# Sheet1.net
KiCad netlist of a schematic drawn in Altium Designer
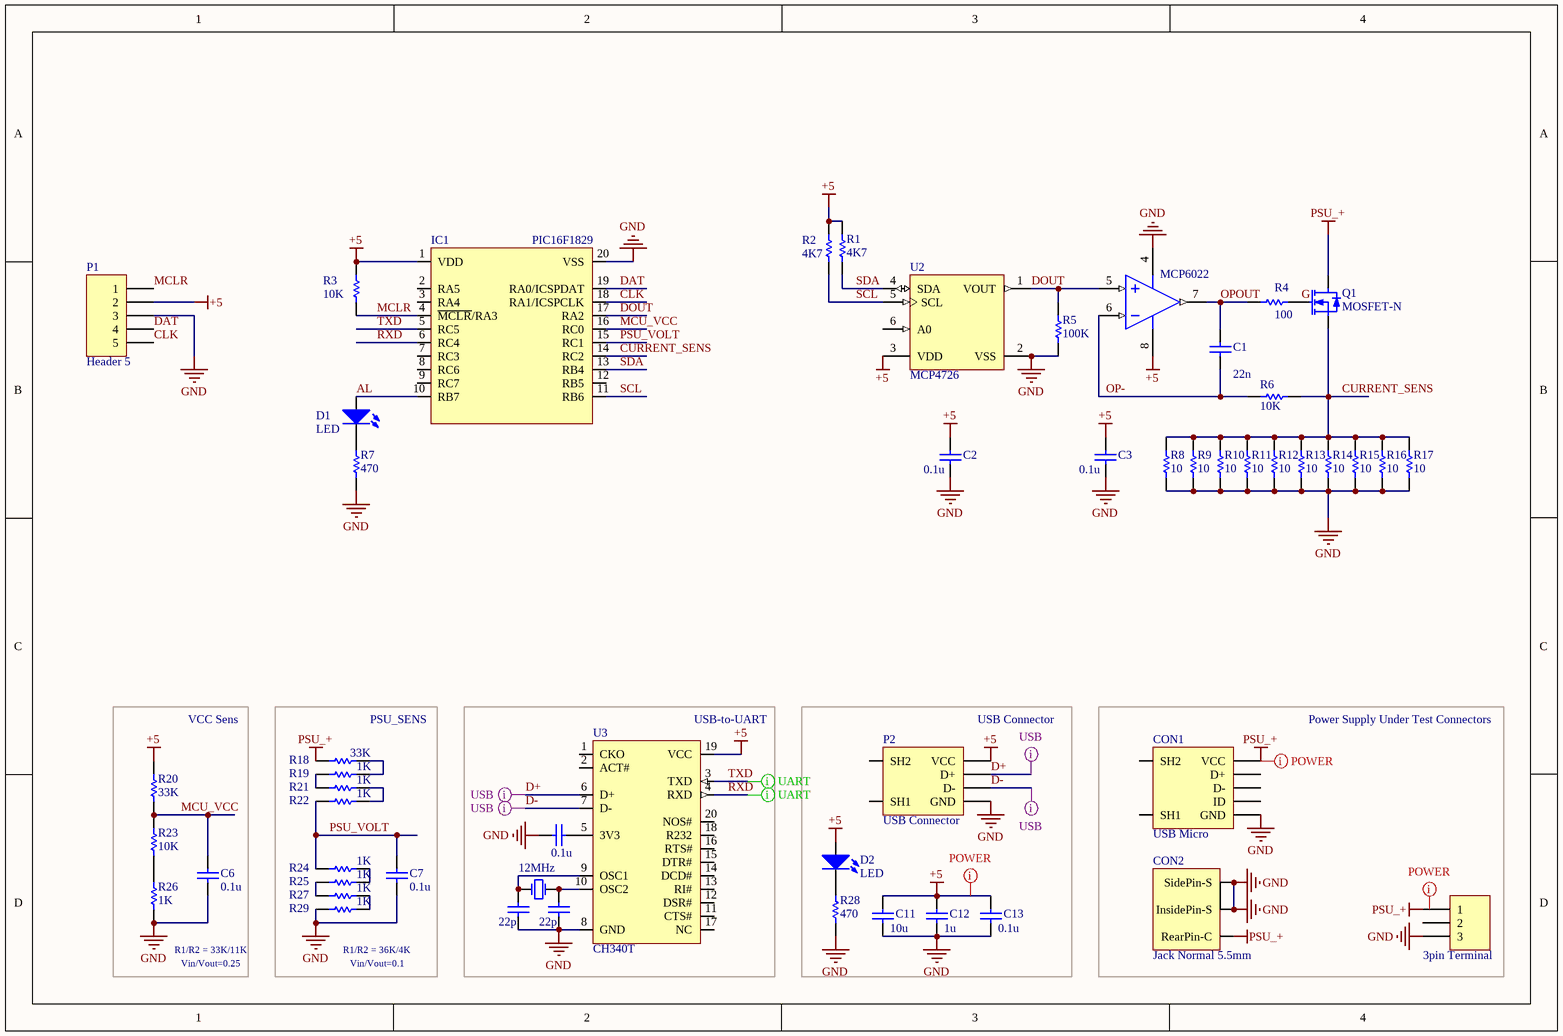
[diagram p0: Sheet1.SchDoc]

(export (version "E")
  (design (tool "Eeschema 10.0.6"))
  (components
    (comp (ref "C1")
      (value "22n")
      (footprint "Moji Footprintovi:0805")
      (description "Capacitor")
      (fields (field (name "Comment") "Cap") (field (name "PUBLISHER") "Altium Limited"))
      (libsource (lib "Moji Schematici") (part "Cap"))
    )
    (comp (ref "C2")
      (value "0.1u")
      (footprint "Moji Footprintovi:0805")
      (description "Capacitor")
      (fields (field (name "Comment") "Cap") (field (name "PUBLISHER") "Altium Limited"))
      (libsource (lib "Moji Schematici") (part "Cap"))
    )
    (comp (ref "C3")
      (value "0.1u")
      (footprint "Moji Footprintovi:0805")
      (description "Capacitor")
      (fields (field (name "Comment") "Cap") (field (name "PUBLISHER") "Altium Limited"))
      (libsource (lib "Moji Schematici") (part "Cap"))
    )
    (comp (ref "C5")
      (value "0.1u")
      (footprint "Moji Footprintovi:0805")
      (description "Capacitor")
      (fields (field (name "Comment") "Cap") (field (name "PUBLISHER") "Altium Limited"))
      (libsource (lib "Moji Schematici") (part "Cap"))
    )
    (comp (ref "C6")
      (value "0.1u")
      (footprint "Moji Footprintovi:0805")
      (description "Capacitor")
      (fields (field (name "Comment") "Cap") (field (name "PUBLISHER") "Altium Limited"))
      (libsource (lib "Moji Schematici") (part "Cap"))
    )
    (comp (ref "C7")
      (value "0.1u")
      (footprint "Moji Footprintovi:0805")
      (description "Capacitor")
      (fields (field (name "Comment") "Cap") (field (name "PUBLISHER") "Altium Limited"))
      (libsource (lib "Moji Schematici") (part "Cap"))
    )
    (comp (ref "C8")
      (value "22p")
      (footprint "Moji Footprintovi:0805")
      (description "Capacitor")
      (fields (field (name "Comment") "Cap") (field (name "PUBLISHER") "Altium Limited"))
      (libsource (lib "Moji Schematici") (part "Cap"))
    )
    (comp (ref "C9")
      (value "22p")
      (footprint "Moji Footprintovi:0805")
      (description "Capacitor")
      (fields (field (name "Comment") "Cap") (field (name "PUBLISHER") "Altium Limited"))
      (libsource (lib "Moji Schematici") (part "Cap"))
    )
    (comp (ref "C11")
      (value "10u")
      (footprint "Moji Footprintovi:0805")
      (description "Capacitor")
      (fields (field (name "Comment") "Cap") (field (name "PUBLISHER") "Altium Limited"))
      (libsource (lib "Moji Schematici") (part "Cap"))
    )
    (comp (ref "C12")
      (value "1u")
      (footprint "Moji Footprintovi:0805")
      (description "Capacitor")
      (fields (field (name "Comment") "Cap") (field (name "PUBLISHER") "Altium Limited"))
      (libsource (lib "Moji Schematici") (part "Cap"))
    )
    (comp (ref "C13")
      (value "0.1u")
      (footprint "Moji Footprintovi:0805")
      (description "Capacitor")
      (fields (field (name "Comment") "Cap") (field (name "PUBLISHER") "Altium Limited"))
      (libsource (lib "Moji Schematici") (part "Cap"))
    )
    (comp (ref "CON1")
      (value "USB Micro")
      (footprint "Moji Footprintovi:USB Micro SMD")
      (description "Header, 4-Pin")
      (fields (field (name "PUBLISHER") "Altium Limited"))
      (libsource (lib "Moji Schematici") (part "USB Micro TH"))
    )
    (comp (ref "CON2")
      (value "Jack Normal 5.5mm")
      (footprint "Jack Normal")
      (description "DC Jack - Center and Side pin Shorted!")
      (libsource (lib "Moji Schematici") (part "Jack Normal 5.5mm"))
    )
    (comp (ref "CON3")
      (value "3pin Terminal")
      (footprint "Terminal 3")
      (description "Header, 3-Pin")
      (fields (field (name "PUBLISHER") "Altium Limited"))
      (libsource (lib "Moji Schematici") (part "Terminal 3"))
    )
    (comp (ref "D1")
      (value "LED")
      (footprint "Moji Footprintovi:LED 5mm [2.54 pin]")
      (description "Typical RED GaAs LED")
      (fields (field (name "PUBLISHER") "Altium Limited"))
      (libsource (lib "Moji Schematici") (part "LED"))
    )
    (comp (ref "D2")
      (value "LED")
      (footprint "Moji Footprintovi:0805 -  LED")
      (description "Typical RED GaAs LED")
      (fields (field (name "PUBLISHER") "Altium Limited"))
      (libsource (lib "Moji Schematici") (part "LED"))
    )
    (comp (ref "IC1")
      (value "PIC16F1829")
      (footprint "Moji Footprintovi:SOP20")
      (libsource (lib "Moji Schematici") (part "PIC16F1829"))
    )
    (comp (ref "P1")
      (value "Header 5")
      (footprint "Moji Footprintovi:Header 5x1")
      (description "Header, 5-Pin")
      (fields (field (name "PUBLISHER") "Altium Limited"))
      (libsource (lib "Moji Schematici") (part "Header 5"))
    )
    (comp (ref "P2")
      (value "USB Connector")
      (footprint "Moji Footprintovi:USB Mini SMD TOP")
      (description "Header, 4-Pin")
      (fields (field (name "PUBLISHER") "Altium Limited"))
      (libsource (lib "Moji Schematici") (part "USB Connector"))
    )
    (comp (ref "Q1")
      (value "MOSFET-N")
      (footprint "Moji Footprintovi:TO-220 w HS2")
      (description "N-Channel MOSFET")
      (fields (field (name "PUBLISHER") "Altium Limited"))
      (libsource (lib "Moji Schematici") (part "MOSFET-N"))
    )
    (comp (ref "R1")
      (value "4K7")
      (footprint "Moji Footprintovi:Axial 0.4")
      (description "Resistor")
      (fields (field (name "Comment") "Res") (field (name "PUBLISHER") "Altium Limited"))
      (libsource (lib "Moji Schematici") (part "Res"))
    )
    (comp (ref "R2")
      (value "4K7")
      (footprint "Moji Footprintovi:Axial 0.4")
      (description "Resistor")
      (fields (field (name "Comment") "Res") (field (name "PUBLISHER") "Altium Limited"))
      (libsource (lib "Moji Schematici") (part "Res"))
    )
    (comp (ref "R3")
      (value "10K")
      (footprint "Moji Footprintovi:0805")
      (description "Resistor")
      (fields (field (name "Comment") "Res") (field (name "PUBLISHER") "Altium Limited"))
      (libsource (lib "Moji Schematici") (part "Res"))
    )
    (comp (ref "R4")
      (value "100")
      (footprint "Moji Footprintovi:0805")
      (description "Resistor")
      (fields (field (name "Comment") "Res") (field (name "PUBLISHER") "Altium Limited"))
      (libsource (lib "Moji Schematici") (part "Res"))
    )
    (comp (ref "R5")
      (value "100K")
      (footprint "Moji Footprintovi:Axial 0.4")
      (description "Resistor")
      (fields (field (name "Comment") "Res") (field (name "PUBLISHER") "Altium Limited"))
      (libsource (lib "Moji Schematici") (part "Res"))
    )
    (comp (ref "R6")
      (value "10K")
      (footprint "Moji Footprintovi:0805")
      (description "Resistor")
      (fields (field (name "Comment") "Res") (field (name "PUBLISHER") "Altium Limited"))
      (libsource (lib "Moji Schematici") (part "Res"))
    )
    (comp (ref "R7")
      (value "470")
      (footprint "Moji Footprintovi:Axial 0.4")
      (description "Resistor")
      (fields (field (name "Comment") "Res") (field (name "PUBLISHER") "Altium Limited"))
      (libsource (lib "Moji Schematici") (part "Res"))
    )
    (comp (ref "R8")
      (value "10")
      (footprint "Moji Footprintovi:Axial 0.4")
      (description "Resistor")
      (fields (field (name "Comment") "Res") (field (name "PUBLISHER") "Altium Limited"))
      (libsource (lib "Moji Schematici") (part "Res"))
    )
    (comp (ref "R9")
      (value "10")
      (footprint "Moji Footprintovi:Axial 0.4")
      (description "Resistor")
      (fields (field (name "Comment") "Res") (field (name "PUBLISHER") "Altium Limited"))
      (libsource (lib "Moji Schematici") (part "Res"))
    )
    (comp (ref "R10")
      (value "10")
      (footprint "Moji Footprintovi:Axial 0.4")
      (description "Resistor")
      (fields (field (name "Comment") "Res") (field (name "PUBLISHER") "Altium Limited"))
      (libsource (lib "Moji Schematici") (part "Res"))
    )
    (comp (ref "R11")
      (value "10")
      (footprint "Moji Footprintovi:Axial 0.4")
      (description "Resistor")
      (fields (field (name "Comment") "Res") (field (name "PUBLISHER") "Altium Limited"))
      (libsource (lib "Moji Schematici") (part "Res"))
    )
    (comp (ref "R12")
      (value "10")
      (footprint "Moji Footprintovi:Axial 0.4")
      (description "Resistor")
      (fields (field (name "Comment") "Res") (field (name "PUBLISHER") "Altium Limited"))
      (libsource (lib "Moji Schematici") (part "Res"))
    )
    (comp (ref "R13")
      (value "10")
      (footprint "Moji Footprintovi:Axial 0.4")
      (description "Resistor")
      (fields (field (name "Comment") "Res") (field (name "PUBLISHER") "Altium Limited"))
      (libsource (lib "Moji Schematici") (part "Res"))
    )
    (comp (ref "R14")
      (value "10")
      (footprint "Moji Footprintovi:Axial 0.4")
      (description "Resistor")
      (fields (field (name "Comment") "Res") (field (name "PUBLISHER") "Altium Limited"))
      (libsource (lib "Moji Schematici") (part "Res"))
    )
    (comp (ref "R15")
      (value "10")
      (footprint "Moji Footprintovi:Axial 0.4")
      (description "Resistor")
      (fields (field (name "Comment") "Res") (field (name "PUBLISHER") "Altium Limited"))
      (libsource (lib "Moji Schematici") (part "Res"))
    )
    (comp (ref "R16")
      (value "10")
      (footprint "Moji Footprintovi:Axial 0.4")
      (description "Resistor")
      (fields (field (name "Comment") "Res") (field (name "PUBLISHER") "Altium Limited"))
      (libsource (lib "Moji Schematici") (part "Res"))
    )
    (comp (ref "R17")
      (value "10")
      (footprint "Moji Footprintovi:Axial 0.4")
      (description "Resistor")
      (fields (field (name "Comment") "Res") (field (name "PUBLISHER") "Altium Limited"))
      (libsource (lib "Moji Schematici") (part "Res"))
    )
    (comp (ref "R18")
      (value "33K")
      (footprint "Moji Footprintovi:0805")
      (description "Resistor")
      (fields (field (name "Comment") "Res") (field (name "PUBLISHER") "Altium Limited"))
      (libsource (lib "Moji Schematici") (part "Res"))
    )
    (comp (ref "R19")
      (value "1K")
      (footprint "Moji Footprintovi:0805")
      (description "Resistor")
      (fields (field (name "Comment") "Res") (field (name "PUBLISHER") "Altium Limited"))
      (libsource (lib "Moji Schematici") (part "Res"))
    )
    (comp (ref "R20")
      (value "33K")
      (footprint "Moji Footprintovi:0805")
      (description "Resistor")
      (fields (field (name "Comment") "Res") (field (name "PUBLISHER") "Altium Limited"))
      (libsource (lib "Moji Schematici") (part "Res"))
    )
    (comp (ref "R21")
      (value "1K")
      (footprint "Moji Footprintovi:0805")
      (description "Resistor")
      (fields (field (name "Comment") "Res") (field (name "PUBLISHER") "Altium Limited"))
      (libsource (lib "Moji Schematici") (part "Res"))
    )
    (comp (ref "R22")
      (value "1K")
      (footprint "Moji Footprintovi:0805")
      (description "Resistor")
      (fields (field (name "Comment") "Res") (field (name "PUBLISHER") "Altium Limited"))
      (libsource (lib "Moji Schematici") (part "Res"))
    )
    (comp (ref "R23")
      (value "10K")
      (footprint "Moji Footprintovi:0805")
      (description "Resistor")
      (fields (field (name "Comment") "Res") (field (name "PUBLISHER") "Altium Limited"))
      (libsource (lib "Moji Schematici") (part "Res"))
    )
    (comp (ref "R24")
      (value "1K")
      (footprint "Moji Footprintovi:0805")
      (description "Resistor")
      (fields (field (name "Comment") "Res") (field (name "PUBLISHER") "Altium Limited"))
      (libsource (lib "Moji Schematici") (part "Res"))
    )
    (comp (ref "R25")
      (value "1K")
      (footprint "Moji Footprintovi:0805")
      (description "Resistor")
      (fields (field (name "Comment") "Res") (field (name "PUBLISHER") "Altium Limited"))
      (libsource (lib "Moji Schematici") (part "Res"))
    )
    (comp (ref "R26")
      (value "1K")
      (footprint "Moji Footprintovi:0805")
      (description "Resistor")
      (fields (field (name "Comment") "Res") (field (name "PUBLISHER") "Altium Limited"))
      (libsource (lib "Moji Schematici") (part "Res"))
    )
    (comp (ref "R27")
      (value "1K")
      (footprint "Moji Footprintovi:0805")
      (description "Resistor")
      (fields (field (name "Comment") "Res") (field (name "PUBLISHER") "Altium Limited"))
      (libsource (lib "Moji Schematici") (part "Res"))
    )
    (comp (ref "R28")
      (value "470")
      (footprint "Moji Footprintovi:0805")
      (description "Resistor")
      (fields (field (name "Comment") "Res") (field (name "PUBLISHER") "Altium Limited"))
      (libsource (lib "Moji Schematici") (part "Res"))
    )
    (comp (ref "R29")
      (value "1K")
      (footprint "Moji Footprintovi:0805")
      (description "Resistor")
      (fields (field (name "Comment") "Res") (field (name "PUBLISHER") "Altium Limited"))
      (libsource (lib "Moji Schematici") (part "Res"))
    )
    (comp (ref "U1")
      (value "MCP6022")
      (footprint "PDIP300-P8")
      (description "Rail-to-Rail Input/Output, 10 MHz Operational Amplifier, 8-Pin PDIP, Industrial Temperature")
      (fields (field (name "PUBLISHER") "Altium Limited"))
      (libsource (lib "Microchip Linear Devices") (part "MCP6022-I/P"))
    )
    (comp (ref "U2")
      (value "MCP4726")
      (footprint "SOT-23-CH6_N")
      (fields (field (name "PUBLISHER") "Altium Limited"))
      (libsource (lib "Microchip Mixed Signal") (part "MCP4725A2T-E/CH"))
    )
    (comp (ref "U3")
      (value "CH340T")
      (footprint "Moji Footprintovi:SOP20-5.30mm-0.65pitch")
      (description "CH340T USB-to-UART")
      (libsource (lib "Moji Schematici") (part "CH340T"))
    )
    (comp (ref "Y1")
      (value "12MHz")
      (footprint "HC-49S")
      (description "Crystal Oscillator")
      (fields (field (name "PUBLISHER") "Altium Limited"))
      (libsource (lib "Moji Schematici") (part "XTAL"))
    )
  )
  (nets
    (net (code "1") (name "+5") (class "Default")
      (node (ref "C11") (pin "2") (pinfunction "2_2") (pintype "passive"))
      (node (ref "C12") (pin "2") (pinfunction "2_2") (pintype "passive"))
      (node (ref "C13") (pin "2") (pinfunction "2_2") (pintype "passive"))
      (node (ref "C2") (pin "2") (pinfunction "2_2") (pintype "passive"))
      (node (ref "C3") (pin "2") (pinfunction "2_2") (pintype "passive"))
      (node (ref "D2") (pin "A") (pinfunction "A_A") (pintype "passive"))
      (node (ref "IC1") (pin "1") (pinfunction "VDD_1") (pintype "passive"))
      (node (ref "P1") (pin "2") (pinfunction "2_2") (pintype "passive"))
      (node (ref "P2") (pin "VCC") (pinfunction "VCC_VCC") (pintype "passive"))
      (node (ref "R1") (pin "2") (pinfunction "2_2") (pintype "passive"))
      (node (ref "R2") (pin "2") (pinfunction "2_2") (pintype "passive"))
      (node (ref "R20") (pin "2") (pinfunction "2_2") (pintype "passive"))
      (node (ref "R3") (pin "2") (pinfunction "2_2") (pintype "passive"))
      (node (ref "U1") (pin "8") (pinfunction "VDD_8") (pintype "power_in"))
      (node (ref "U2") (pin "3") (pinfunction "VDD_3") (pintype "power_in"))
      (node (ref "U3") (pin "19") (pinfunction "VCC_19") (pintype "power_in"))
    )
    (net (code "2") (name "/AL") (class "Default")
      (node (ref "D1") (pin "A") (pinfunction "A_A") (pintype "passive"))
      (node (ref "IC1") (pin "10") (pinfunction "RB7_10") (pintype "passive"))
    )
    (net (code "3") (name "/CLK") (class "Default")
      (node (ref "IC1") (pin "18") (pinfunction "RA1/ICSPCLK_18") (pintype "passive"))
      (node (ref "P1") (pin "5") (pinfunction "5_5") (pintype "passive"))
    )
    (net (code "4") (name "/CURRENT_SENS") (class "Default")
      (node (ref "IC1") (pin "14") (pinfunction "RC2_14") (pintype "passive"))
      (node (ref "Q1") (pin "3") (pinfunction "S_3") (pintype "passive"))
      (node (ref "R10") (pin "2") (pinfunction "2_2") (pintype "passive"))
      (node (ref "R11") (pin "2") (pinfunction "2_2") (pintype "passive"))
      (node (ref "R12") (pin "2") (pinfunction "2_2") (pintype "passive"))
      (node (ref "R13") (pin "2") (pinfunction "2_2") (pintype "passive"))
      (node (ref "R14") (pin "2") (pinfunction "2_2") (pintype "passive"))
      (node (ref "R15") (pin "2") (pinfunction "2_2") (pintype "passive"))
      (node (ref "R16") (pin "2") (pinfunction "2_2") (pintype "passive"))
      (node (ref "R17") (pin "2") (pinfunction "2_2") (pintype "passive"))
      (node (ref "R6") (pin "2") (pinfunction "2_2") (pintype "passive"))
      (node (ref "R8") (pin "2") (pinfunction "2_2") (pintype "passive"))
      (node (ref "R9") (pin "2") (pinfunction "2_2") (pintype "passive"))
    )
    (net (code "5") (name "/D+") (class "Default")
      (node (ref "P2") (pin "D+") (pinfunction "D+_D+") (pintype "passive"))
      (node (ref "U3") (pin "6") (pinfunction "D+_6") (pintype "passive"))
    )
    (net (code "6") (name "/D-") (class "Default")
      (node (ref "P2") (pin "D-") (pinfunction "D-_D-") (pintype "passive"))
      (node (ref "U3") (pin "7") (pinfunction "D-_7") (pintype "passive"))
    )
    (net (code "7") (name "/DAT") (class "Default")
      (node (ref "IC1") (pin "19") (pinfunction "RA0/ICSPDAT_19") (pintype "passive"))
      (node (ref "P1") (pin "4") (pinfunction "4_4") (pintype "passive"))
    )
    (net (code "8") (name "/DOUT") (class "Default")
      (node (ref "IC1") (pin "17") (pinfunction "RA2_17") (pintype "passive"))
      (node (ref "R5") (pin "2") (pinfunction "2_2") (pintype "passive"))
      (node (ref "U1") (pin "5") (pinfunction "VINB+_5") (pintype "input"))
      (node (ref "U2") (pin "1") (pinfunction "VOUT_1") (pintype "output"))
    )
    (net (code "9") (name "/G") (class "Default")
      (node (ref "Q1") (pin "1") (pinfunction "G_1") (pintype "passive"))
      (node (ref "R4") (pin "2") (pinfunction "2_2") (pintype "passive"))
    )
    (net (code "10") (name "/MCLR") (class "Default")
      (node (ref "IC1") (pin "4") (pinfunction "~{MCLR}/RA3_4") (pintype "passive"))
      (node (ref "P1") (pin "1") (pinfunction "1_1") (pintype "passive"))
      (node (ref "R3") (pin "1") (pinfunction "1_1") (pintype "passive"))
    )
    (net (code "11") (name "/MCU_VCC") (class "Default")
      (node (ref "C6") (pin "2") (pinfunction "2_2") (pintype "passive"))
      (node (ref "IC1") (pin "16") (pinfunction "RC0_16") (pintype "passive"))
      (node (ref "R20") (pin "1") (pinfunction "1_1") (pintype "passive"))
      (node (ref "R23") (pin "2") (pinfunction "2_2") (pintype "passive"))
    )
    (net (code "12") (name "/OP-") (class "Default")
      (node (ref "C1") (pin "1") (pinfunction "1_1") (pintype "passive"))
      (node (ref "R6") (pin "1") (pinfunction "1_1") (pintype "passive"))
      (node (ref "U1") (pin "6") (pinfunction "VINB-_6") (pintype "input"))
    )
    (net (code "13") (name "/OPOUT") (class "Default")
      (node (ref "C1") (pin "2") (pinfunction "2_2") (pintype "passive"))
      (node (ref "R4") (pin "1") (pinfunction "1_1") (pintype "passive"))
      (node (ref "U1") (pin "7") (pinfunction "VOUTB_7") (pintype "output"))
    )
    (net (code "14") (name "/PSU_VOLT") (class "Default")
      (node (ref "C7") (pin "2") (pinfunction "2_2") (pintype "passive"))
      (node (ref "IC1") (pin "15") (pinfunction "RC1_15") (pintype "passive"))
      (node (ref "R22") (pin "2") (pinfunction "2_2") (pintype "passive"))
      (node (ref "R24") (pin "2") (pinfunction "2_2") (pintype "passive"))
    )
    (net (code "15") (name "/RXD") (class "Default")
      (node (ref "IC1") (pin "6") (pinfunction "RC4_6") (pintype "passive"))
      (node (ref "U3") (pin "4") (pinfunction "RXD_4") (pintype "output"))
    )
    (net (code "16") (name "/SCL") (class "Default")
      (node (ref "IC1") (pin "11") (pinfunction "RB6_11") (pintype "passive"))
      (node (ref "R2") (pin "1") (pinfunction "1_1") (pintype "passive"))
      (node (ref "U2") (pin "5") (pinfunction "SCL_5") (pintype "input"))
    )
    (net (code "17") (name "/SDA") (class "Default")
      (node (ref "IC1") (pin "13") (pinfunction "RB4_13") (pintype "passive"))
      (node (ref "R1") (pin "1") (pinfunction "1_1") (pintype "passive"))
      (node (ref "U2") (pin "4") (pinfunction "SDA_4") (pintype "bidirectional"))
    )
    (net (code "18") (name "/TXD") (class "Default")
      (node (ref "IC1") (pin "5") (pinfunction "RC5_5") (pintype "passive"))
      (node (ref "U3") (pin "3") (pinfunction "TXD_3") (pintype "input"))
    )
    (net (code "19") (name "GND") (class "Default")
      (node (ref "C11") (pin "1") (pinfunction "1_1") (pintype "passive"))
      (node (ref "C12") (pin "1") (pinfunction "1_1") (pintype "passive"))
      (node (ref "C13") (pin "1") (pinfunction "1_1") (pintype "passive"))
      (node (ref "C2") (pin "1") (pinfunction "1_1") (pintype "passive"))
      (node (ref "C3") (pin "1") (pinfunction "1_1") (pintype "passive"))
      (node (ref "C5") (pin "2") (pinfunction "2_2") (pintype "passive"))
      (node (ref "C6") (pin "1") (pinfunction "1_1") (pintype "passive"))
      (node (ref "C7") (pin "1") (pinfunction "1_1") (pintype "passive"))
      (node (ref "C8") (pin "1") (pinfunction "1_1") (pintype "passive"))
      (node (ref "C9") (pin "1") (pinfunction "1_1") (pintype "passive"))
      (node (ref "CON1") (pin "GND") (pinfunction "GND_GND") (pintype "passive"))
      (node (ref "CON2") (pin "InsidePin") (pinfunction "InsidePin-S_InsidePin") (pintype "passive"))
      (node (ref "CON2") (pin "SidePin") (pinfunction "SidePin-S_SidePin") (pintype "passive"))
      (node (ref "CON3") (pin "3") (pinfunction "3_3") (pintype "passive"))
      (node (ref "IC1") (pin "20") (pinfunction "VSS_20") (pintype "passive"))
      (node (ref "P1") (pin "3") (pinfunction "3_3") (pintype "passive"))
      (node (ref "P2") (pin "GND") (pinfunction "GND_GND") (pintype "passive"))
      (node (ref "R10") (pin "1") (pinfunction "1_1") (pintype "passive"))
      (node (ref "R11") (pin "1") (pinfunction "1_1") (pintype "passive"))
      (node (ref "R12") (pin "1") (pinfunction "1_1") (pintype "passive"))
      (node (ref "R13") (pin "1") (pinfunction "1_1") (pintype "passive"))
      (node (ref "R14") (pin "1") (pinfunction "1_1") (pintype "passive"))
      (node (ref "R15") (pin "1") (pinfunction "1_1") (pintype "passive"))
      (node (ref "R16") (pin "1") (pinfunction "1_1") (pintype "passive"))
      (node (ref "R17") (pin "1") (pinfunction "1_1") (pintype "passive"))
      (node (ref "R26") (pin "1") (pinfunction "1_1") (pintype "passive"))
      (node (ref "R28") (pin "1") (pinfunction "1_1") (pintype "passive"))
      (node (ref "R29") (pin "2") (pinfunction "2_2") (pintype "passive"))
      (node (ref "R5") (pin "1") (pinfunction "1_1") (pintype "passive"))
      (node (ref "R7") (pin "1") (pinfunction "1_1") (pintype "passive"))
      (node (ref "R8") (pin "1") (pinfunction "1_1") (pintype "passive"))
      (node (ref "R9") (pin "1") (pinfunction "1_1") (pintype "passive"))
      (node (ref "U1") (pin "4") (pinfunction "VSS_4") (pintype "power_in"))
      (node (ref "U2") (pin "2") (pinfunction "VSS_2") (pintype "power_in"))
      (node (ref "U3") (pin "8") (pinfunction "GND_8") (pintype "power_in"))
    )
    (net (code "20") (name "Net-(D1-PadK)") (class "Default")
      (node (ref "D1") (pin "K") (pinfunction "K_K") (pintype "passive"))
      (node (ref "R7") (pin "2") (pinfunction "2_2") (pintype "passive"))
    )
    (net (code "21") (name "Net-(D2-PadK)") (class "Default")
      (node (ref "D2") (pin "K") (pinfunction "K_K") (pintype "passive"))
      (node (ref "R28") (pin "2") (pinfunction "2_2") (pintype "passive"))
    )
    (net (code "22") (name "Net-(R18-Pad1)") (class "Default")
      (node (ref "R18") (pin "1") (pinfunction "1_1") (pintype "passive"))
      (node (ref "R19") (pin "1") (pinfunction "1_1") (pintype "passive"))
    )
    (net (code "23") (name "Net-(R19-Pad2)") (class "Default")
      (node (ref "R19") (pin "2") (pinfunction "2_2") (pintype "passive"))
      (node (ref "R21") (pin "2") (pinfunction "2_2") (pintype "passive"))
    )
    (net (code "24") (name "Net-(R21-Pad1)") (class "Default")
      (node (ref "R21") (pin "1") (pinfunction "1_1") (pintype "passive"))
      (node (ref "R22") (pin "1") (pinfunction "1_1") (pintype "passive"))
    )
    (net (code "25") (name "Net-(R23-Pad1)") (class "Default")
      (node (ref "R23") (pin "1") (pinfunction "1_1") (pintype "passive"))
      (node (ref "R26") (pin "2") (pinfunction "2_2") (pintype "passive"))
    )
    (net (code "26") (name "Net-(R24-Pad1)") (class "Default")
      (node (ref "R24") (pin "1") (pinfunction "1_1") (pintype "passive"))
      (node (ref "R25") (pin "1") (pinfunction "1_1") (pintype "passive"))
    )
    (net (code "27") (name "Net-(R25-Pad2)") (class "Default")
      (node (ref "R25") (pin "2") (pinfunction "2_2") (pintype "passive"))
      (node (ref "R27") (pin "2") (pinfunction "2_2") (pintype "passive"))
    )
    (net (code "28") (name "Net-(R27-Pad1)") (class "Default")
      (node (ref "R27") (pin "1") (pinfunction "1_1") (pintype "passive"))
      (node (ref "R29") (pin "1") (pinfunction "1_1") (pintype "passive"))
    )
    (net (code "29") (name "Net-(U3-3V3)") (class "Default")
      (node (ref "C5") (pin "1") (pinfunction "1_1") (pintype "passive"))
      (node (ref "U3") (pin "5") (pinfunction "3V3_5") (pintype "power_in"))
    )
    (net (code "30") (name "Net-(U3-OSC1)") (class "Default")
      (node (ref "C8") (pin "2") (pinfunction "2_2") (pintype "passive"))
      (node (ref "U3") (pin "9") (pinfunction "OSC1_9") (pintype "passive"))
      (node (ref "Y1") (pin "1") (pinfunction "OSC1_1") (pintype "passive"))
    )
    (net (code "31") (name "Net-(U3-OSC2)") (class "Default")
      (node (ref "C9") (pin "2") (pinfunction "2_2") (pintype "passive"))
      (node (ref "U3") (pin "10") (pinfunction "OSC2_10") (pintype "passive"))
      (node (ref "Y1") (pin "2") (pinfunction "OSC2_2") (pintype "passive"))
    )
    (net (code "32") (name "PSU_+") (class "Default")
      (node (ref "CON1") (pin "VCC") (pinfunction "VCC_VCC") (pintype "passive"))
      (node (ref "CON2") (pin "RearPin") (pinfunction "RearPin-C_RearPin") (pintype "passive"))
      (node (ref "CON3") (pin "1") (pinfunction "1_1") (pintype "passive"))
      (node (ref "Q1") (pin "2") (pinfunction "D_2") (pintype "passive"))
      (node (ref "R18") (pin "2") (pinfunction "2_2") (pintype "passive"))
    )
    (net (code "33") (name "unconnected-(CON1-PadD+)") (class "Default")
      (node (ref "CON1") (pin "D+") (pinfunction "D+_D+") (pintype "passive"))
    )
    (net (code "34") (name "unconnected-(CON1-PadD-)") (class "Default")
      (node (ref "CON1") (pin "D-") (pinfunction "D-_D-") (pintype "passive"))
    )
    (net (code "35") (name "unconnected-(CON1-PadID)") (class "Default")
      (node (ref "CON1") (pin "ID") (pinfunction "ID_ID") (pintype "passive"))
    )
    (net (code "36") (name "unconnected-(CON1-PadSH1)") (class "Default")
      (node (ref "CON1") (pin "SH1") (pinfunction "SH1_SH1") (pintype "passive"))
    )
    (net (code "37") (name "unconnected-(CON1-PadSH2)") (class "Default")
      (node (ref "CON1") (pin "SH2") (pinfunction "SH2_SH2") (pintype "passive"))
    )
    (net (code "38") (name "unconnected-(CON3-Pad2)") (class "Default")
      (node (ref "CON3") (pin "2") (pinfunction "2_2") (pintype "passive"))
    )
    (net (code "39") (name "unconnected-(IC1-RA4-Pad3)") (class "Default")
      (node (ref "IC1") (pin "3") (pinfunction "RA4_3") (pintype "passive"))
    )
    (net (code "40") (name "unconnected-(IC1-RA5-Pad2)") (class "Default")
      (node (ref "IC1") (pin "2") (pinfunction "RA5_2") (pintype "passive"))
    )
    (net (code "41") (name "unconnected-(IC1-RB5-Pad12)") (class "Default")
      (node (ref "IC1") (pin "12") (pinfunction "RB5_12") (pintype "passive"))
    )
    (net (code "42") (name "unconnected-(IC1-RC3-Pad7)") (class "Default")
      (node (ref "IC1") (pin "7") (pinfunction "RC3_7") (pintype "passive"))
    )
    (net (code "43") (name "unconnected-(IC1-RC6-Pad8)") (class "Default")
      (node (ref "IC1") (pin "8") (pinfunction "RC6_8") (pintype "passive"))
    )
    (net (code "44") (name "unconnected-(IC1-RC7-Pad9)") (class "Default")
      (node (ref "IC1") (pin "9") (pinfunction "RC7_9") (pintype "passive"))
    )
    (net (code "45") (name "unconnected-(P2-PadSH1)") (class "Default")
      (node (ref "P2") (pin "SH1") (pinfunction "SH1_SH1") (pintype "passive"))
    )
    (net (code "46") (name "unconnected-(P2-PadSH2)") (class "Default")
      (node (ref "P2") (pin "SH2") (pinfunction "SH2_SH2") (pintype "passive"))
    )
    (net (code "47") (name "unconnected-(U2-A0-Pad6)") (class "Default")
      (node (ref "U2") (pin "6") (pinfunction "A0_6") (pintype "input"))
    )
    (net (code "48") (name "unconnected-(U3-ACT#-Pad2)") (class "Default")
      (node (ref "U3") (pin "2") (pinfunction "ACT#_2") (pintype "passive"))
    )
    (net (code "49") (name "unconnected-(U3-CKO-Pad1)") (class "Default")
      (node (ref "U3") (pin "1") (pinfunction "CKO_1") (pintype "passive"))
    )
    (net (code "50") (name "unconnected-(U3-CTS#-Pad11)") (class "Default")
      (node (ref "U3") (pin "11") (pinfunction "CTS#_11") (pintype "passive"))
    )
    (net (code "51") (name "unconnected-(U3-DCD#-Pad14)") (class "Default")
      (node (ref "U3") (pin "14") (pinfunction "DCD#_14") (pintype "passive"))
    )
    (net (code "52") (name "unconnected-(U3-DSR#-Pad12)") (class "Default")
      (node (ref "U3") (pin "12") (pinfunction "DSR#_12") (pintype "passive"))
    )
    (net (code "53") (name "unconnected-(U3-DTR#-Pad15)") (class "Default")
      (node (ref "U3") (pin "15") (pinfunction "DTR#_15") (pintype "passive"))
    )
    (net (code "54") (name "unconnected-(U3-NC-Pad17)") (class "Default")
      (node (ref "U3") (pin "17") (pinfunction "NC_17") (pintype "passive"))
    )
    (net (code "55") (name "unconnected-(U3-NOS#-Pad20)") (class "Default")
      (node (ref "U3") (pin "20") (pinfunction "NOS#_20") (pintype "passive"))
    )
    (net (code "56") (name "unconnected-(U3-R232-Pad18)") (class "Default")
      (node (ref "U3") (pin "18") (pinfunction "R232_18") (pintype "passive"))
    )
    (net (code "57") (name "unconnected-(U3-RI#-Pad13)") (class "Default")
      (node (ref "U3") (pin "13") (pinfunction "RI#_13") (pintype "passive"))
    )
    (net (code "58") (name "unconnected-(U3-RTS#-Pad16)") (class "Default")
      (node (ref "U3") (pin "16") (pinfunction "RTS#_16") (pintype "passive"))
    )
  )
)
